# UserComponents.net
KiCad netlist of a schematic drawn in Altium Designer
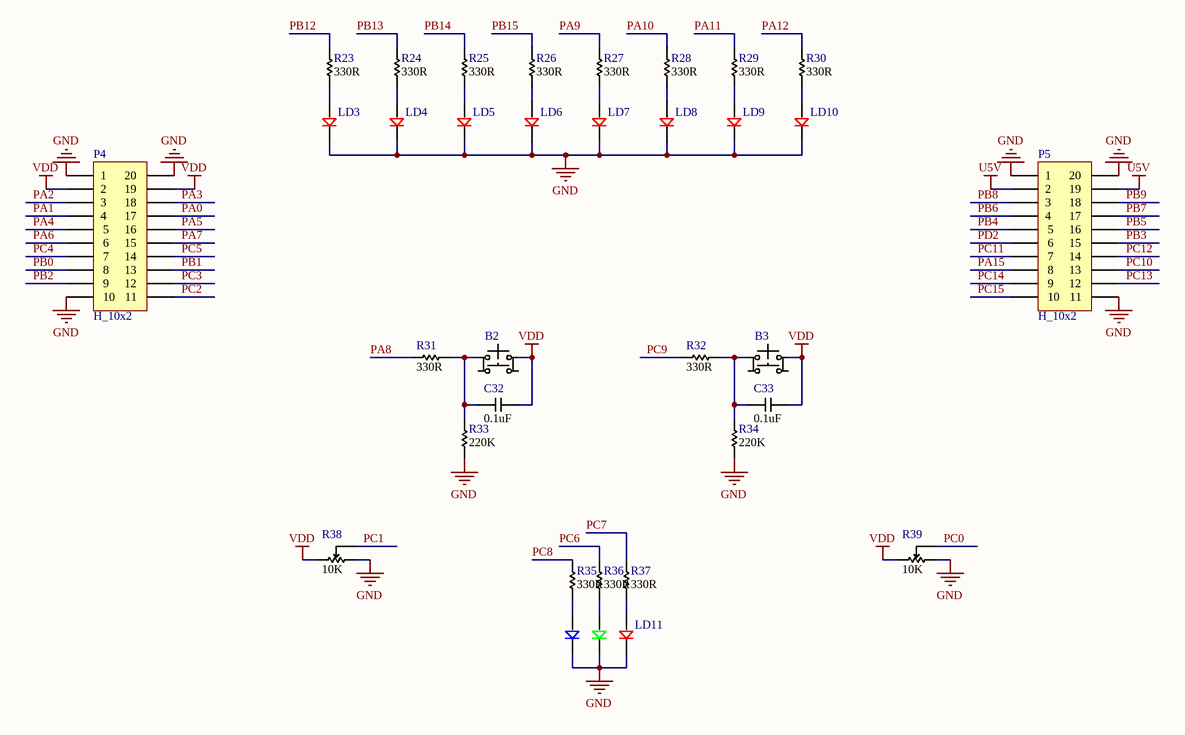
[diagram p0: UserComponents.SchDoc]

(export (version "E")
  (design (tool "Eeschema 10.0.6"))
  (components
    (comp (ref "B2")
      (value "DTSM-65R-V-T/R")
      (footprint "Diptronics_DTSM-65_Red_4")
      (description "Button_SMD_4_6x6x9.5_Diptronics")
      (fields (field (name "MANUFACTURER") "Diptronics"))
      (libsource (lib "Button") (part "DTSM-65R-V-T/R"))
    )
    (comp (ref "B3")
      (value "DTSM-65R-V-T/R")
      (footprint "Diptronics_DTSM-65_Red_4")
      (description "Button_SMD_4_6x6x9.5_Diptronics")
      (fields (field (name "MANUFACTURER") "Diptronics"))
      (libsource (lib "Button") (part "DTSM-65R-V-T/R"))
    )
    (comp (ref "C32")
      (value "0.1uF")
      (footprint "Kemet_0805_X7R")
      (description "Cap_0805_0.1uF_25VDC_Kemet")
      (fields (field (name "MANUFACTURER") "Kemet") (field (name "VOLTAGE") "25VDC"))
      (libsource (lib "Capacitor") (part "C0805C104K3RACTU"))
    )
    (comp (ref "C33")
      (value "0.1uF")
      (footprint "Kemet_0805_X7R")
      (description "Cap_0805_0.1uF_25VDC_Kemet")
      (fields (field (name "MANUFACTURER") "Kemet") (field (name "VOLTAGE") "25VDC"))
      (libsource (lib "Capacitor") (part "C0805C104K3RACTU"))
    )
    (comp (ref "LD3")
      (value "17-21/R6C-AP1Q2L/3T")
      (footprint "Everlight_17-21")
      (description "Led_R_1.7V_25mA_Everlight")
      (fields (field (name "MANUFACTURER") "Everlight"))
      (libsource (lib "LED") (part "17-21/R6C-AP1Q2L/3T"))
    )
    (comp (ref "LD4")
      (value "17-21/R6C-AP1Q2L/3T")
      (footprint "Everlight_17-21")
      (description "Led_R_1.7V_25mA_Everlight")
      (fields (field (name "MANUFACTURER") "Everlight"))
      (libsource (lib "LED") (part "17-21/R6C-AP1Q2L/3T"))
    )
    (comp (ref "LD5")
      (value "17-21/R6C-AP1Q2L/3T")
      (footprint "Everlight_17-21")
      (description "Led_R_1.7V_25mA_Everlight")
      (fields (field (name "MANUFACTURER") "Everlight"))
      (libsource (lib "LED") (part "17-21/R6C-AP1Q2L/3T"))
    )
    (comp (ref "LD6")
      (value "17-21/R6C-AP1Q2L/3T")
      (footprint "Everlight_17-21")
      (description "Led_R_1.7V_25mA_Everlight")
      (fields (field (name "MANUFACTURER") "Everlight"))
      (libsource (lib "LED") (part "17-21/R6C-AP1Q2L/3T"))
    )
    (comp (ref "LD7")
      (value "17-21/R6C-AP1Q2L/3T")
      (footprint "Everlight_17-21")
      (description "Led_R_1.7V_25mA_Everlight")
      (fields (field (name "MANUFACTURER") "Everlight"))
      (libsource (lib "LED") (part "17-21/R6C-AP1Q2L/3T"))
    )
    (comp (ref "LD8")
      (value "17-21/R6C-AP1Q2L/3T")
      (footprint "Everlight_17-21")
      (description "Led_R_1.7V_25mA_Everlight")
      (fields (field (name "MANUFACTURER") "Everlight"))
      (libsource (lib "LED") (part "17-21/R6C-AP1Q2L/3T"))
    )
    (comp (ref "LD9")
      (value "17-21/R6C-AP1Q2L/3T")
      (footprint "Everlight_17-21")
      (description "Led_R_1.7V_25mA_Everlight")
      (fields (field (name "MANUFACTURER") "Everlight"))
      (libsource (lib "LED") (part "17-21/R6C-AP1Q2L/3T"))
    )
    (comp (ref "LD10")
      (value "17-21/R6C-AP1Q2L/3T")
      (footprint "Everlight_17-21")
      (description "Led_R_1.7V_25mA_Everlight")
      (fields (field (name "MANUFACTURER") "Everlight"))
      (libsource (lib "LED") (part "17-21/R6C-AP1Q2L/3T"))
    )
    (comp (ref "LD11")
      (value "HLAF5060H248BS36FU76GCS1")
      (footprint "Honglitronic_5050")
      (description "Led_RGB_1.8-2.8-2.8V_3x90mA_Honglitronic")
      (fields (field (name "MANUFACTURER") "Honglitronic"))
      (libsource (lib "LED") (part "HLAF5060H248BS36FU76GCS1"))
    )
    (comp (ref "P4")
      (value "H_10x2")
      (footprint "HEADER_HDRV20W65P254_10X2_2540X508H945")
      (description "Head_10x2_2.54")
      (libsource (lib "Header") (part "H_10x2"))
    )
    (comp (ref "P5")
      (value "H_10x2")
      (footprint "HEADER_HDRV20W65P254_10X2_2540X508H945")
      (description "Head_10x2_2.54")
      (libsource (lib "Header") (part "H_10x2"))
    )
    (comp (ref "R23")
      (value "330R")
      (footprint "VISHAY_RESC205X125X50L35_30N")
      (description "Res_0805_0R_1/8W_Vishay")
      (fields (field (name "MANUFACTURER") "Vishay") (field (name "POWER") "1/8W"))
      (libsource (lib "Resistor") (part "CRCW08050000Z0EA"))
    )
    (comp (ref "R24")
      (value "330R")
      (footprint "VISHAY_RESC205X125X50L35_30N")
      (description "Res_0805_0R_1/8W_Vishay")
      (fields (field (name "MANUFACTURER") "Vishay") (field (name "POWER") "1/8W"))
      (libsource (lib "Resistor") (part "CRCW08050000Z0EA"))
    )
    (comp (ref "R25")
      (value "330R")
      (footprint "VISHAY_RESC205X125X50L35_30N")
      (description "Res_0805_0R_1/8W_Vishay")
      (fields (field (name "MANUFACTURER") "Vishay") (field (name "POWER") "1/8W"))
      (libsource (lib "Resistor") (part "CRCW08050000Z0EA"))
    )
    (comp (ref "R26")
      (value "330R")
      (footprint "VISHAY_RESC205X125X50L35_30N")
      (description "Res_0805_0R_1/8W_Vishay")
      (fields (field (name "MANUFACTURER") "Vishay") (field (name "POWER") "1/8W"))
      (libsource (lib "Resistor") (part "CRCW08050000Z0EA"))
    )
    (comp (ref "R27")
      (value "330R")
      (footprint "VISHAY_RESC205X125X50L35_30N")
      (description "Res_0805_0R_1/8W_Vishay")
      (fields (field (name "MANUFACTURER") "Vishay") (field (name "POWER") "1/8W"))
      (libsource (lib "Resistor") (part "CRCW08050000Z0EA"))
    )
    (comp (ref "R28")
      (value "330R")
      (footprint "VISHAY_RESC205X125X50L35_30N")
      (description "Res_0805_0R_1/8W_Vishay")
      (fields (field (name "MANUFACTURER") "Vishay") (field (name "POWER") "1/8W"))
      (libsource (lib "Resistor") (part "CRCW08050000Z0EA"))
    )
    (comp (ref "R29")
      (value "330R")
      (footprint "VISHAY_RESC205X125X50L35_30N")
      (description "Res_0805_0R_1/8W_Vishay")
      (fields (field (name "MANUFACTURER") "Vishay") (field (name "POWER") "1/8W"))
      (libsource (lib "Resistor") (part "CRCW08050000Z0EA"))
    )
    (comp (ref "R30")
      (value "330R")
      (footprint "VISHAY_RESC205X125X50L35_30N")
      (description "Res_0805_0R_1/8W_Vishay")
      (fields (field (name "MANUFACTURER") "Vishay") (field (name "POWER") "1/8W"))
      (libsource (lib "Resistor") (part "CRCW08050000Z0EA"))
    )
    (comp (ref "R31")
      (value "330R")
      (footprint "VISHAY_RESC205X125X50L35_30N")
      (description "Res_0805_0R_1/8W_Vishay")
      (fields (field (name "MANUFACTURER") "Vishay") (field (name "POWER") "1/8W"))
      (libsource (lib "Resistor") (part "CRCW08050000Z0EA"))
    )
    (comp (ref "R32")
      (value "330R")
      (footprint "VISHAY_RESC205X125X50L35_30N")
      (description "Res_0805_0R_1/8W_Vishay")
      (fields (field (name "MANUFACTURER") "Vishay") (field (name "POWER") "1/8W"))
      (libsource (lib "Resistor") (part "CRCW08050000Z0EA"))
    )
    (comp (ref "R33")
      (value "220K")
      (footprint "VISHAY_RESC205X125X50L35_30N")
      (description "Res_0805_0R_1/8W_Vishay")
      (fields (field (name "MANUFACTURER") "Vishay") (field (name "POWER") "1/8W"))
      (libsource (lib "Resistor") (part "CRCW08050000Z0EA"))
    )
    (comp (ref "R34")
      (value "220K")
      (footprint "VISHAY_RESC205X125X50L35_30N")
      (description "Res_0805_0R_1/8W_Vishay")
      (fields (field (name "MANUFACTURER") "Vishay") (field (name "POWER") "1/8W"))
      (libsource (lib "Resistor") (part "CRCW08050000Z0EA"))
    )
    (comp (ref "R35")
      (value "330R")
      (footprint "VISHAY_RESC205X125X50L35_30N")
      (description "Res_0805_0R_1/8W_Vishay")
      (fields (field (name "MANUFACTURER") "Vishay") (field (name "POWER") "1/8W"))
      (libsource (lib "Resistor") (part "CRCW08050000Z0EA"))
    )
    (comp (ref "R36")
      (value "330R")
      (footprint "VISHAY_RESC205X125X50L35_30N")
      (description "Res_0805_0R_1/8W_Vishay")
      (fields (field (name "MANUFACTURER") "Vishay") (field (name "POWER") "1/8W"))
      (libsource (lib "Resistor") (part "CRCW08050000Z0EA"))
    )
    (comp (ref "R37")
      (value "330R")
      (footprint "VISHAY_RESC205X125X50L35_30N")
      (description "Res_0805_0R_1/8W_Vishay")
      (fields (field (name "MANUFACTURER") "Vishay") (field (name "POWER") "1/8W"))
      (libsource (lib "Resistor") (part "CRCW08050000Z0EA"))
    )
    (comp (ref "R38")
      (value "10K")
      (footprint "Bonens_3386F")
      (description "Trimpot_10K_Bonens")
      (fields (field (name "MANUFACTURER") "Bonens") (field (name "Comment") "3386F-1-103LF-BN"))
      (libsource (lib "Resistor") (part "3386F-1-103LF-BN"))
    )
    (comp (ref "R39")
      (value "10K")
      (footprint "Bonens_3386F")
      (description "Trimpot_10K_Bonens")
      (fields (field (name "MANUFACTURER") "Bonens") (field (name "Comment") "3386F-1-103LF-BN"))
      (libsource (lib "Resistor") (part "3386F-1-103LF-BN"))
    )
  )
  (nets
    (net (code "1") (name "/PA0") (class "Default")
      (node (ref "P4") (pin "17") (pinfunction "17_17") (pintype "passive"))
    )
    (net (code "2") (name "/PA1") (class "Default")
      (node (ref "P4") (pin "4") (pinfunction "4_4") (pintype "passive"))
    )
    (net (code "3") (name "/PA2") (class "Default")
      (node (ref "P4") (pin "3") (pinfunction "3_3") (pintype "passive"))
    )
    (net (code "4") (name "/PA3") (class "Default")
      (node (ref "P4") (pin "18") (pinfunction "18_18") (pintype "passive"))
    )
    (net (code "5") (name "/PA4") (class "Default")
      (node (ref "P4") (pin "5") (pinfunction "5_5") (pintype "passive"))
    )
    (net (code "6") (name "/PA5") (class "Default")
      (node (ref "P4") (pin "16") (pinfunction "16_16") (pintype "passive"))
    )
    (net (code "7") (name "/PA6") (class "Default")
      (node (ref "P4") (pin "6") (pinfunction "6_6") (pintype "passive"))
    )
    (net (code "8") (name "/PA7") (class "Default")
      (node (ref "P4") (pin "15") (pinfunction "15_15") (pintype "passive"))
    )
    (net (code "9") (name "/PA8") (class "Default")
      (node (ref "R31") (pin "1") (pinfunction "1_1") (pintype "passive"))
    )
    (net (code "10") (name "/PA9") (class "Default")
      (node (ref "R27") (pin "2") (pinfunction "2_2") (pintype "passive"))
    )
    (net (code "11") (name "/PA10") (class "Default")
      (node (ref "R28") (pin "2") (pinfunction "2_2") (pintype "passive"))
    )
    (net (code "12") (name "/PA11") (class "Default")
      (node (ref "R29") (pin "2") (pinfunction "2_2") (pintype "passive"))
    )
    (net (code "13") (name "/PA12") (class "Default")
      (node (ref "R30") (pin "2") (pinfunction "2_2") (pintype "passive"))
    )
    (net (code "14") (name "/PA15") (class "Default")
      (node (ref "P5") (pin "8") (pinfunction "8_8") (pintype "passive"))
    )
    (net (code "15") (name "/PB0") (class "Default")
      (node (ref "P4") (pin "8") (pinfunction "8_8") (pintype "passive"))
    )
    (net (code "16") (name "/PB1") (class "Default")
      (node (ref "P4") (pin "13") (pinfunction "13_13") (pintype "passive"))
    )
    (net (code "17") (name "/PB2") (class "Default")
      (node (ref "P4") (pin "9") (pinfunction "9_9") (pintype "passive"))
    )
    (net (code "18") (name "/PB3") (class "Default")
      (node (ref "P5") (pin "15") (pinfunction "15_15") (pintype "passive"))
    )
    (net (code "19") (name "/PB4") (class "Default")
      (node (ref "P5") (pin "5") (pinfunction "5_5") (pintype "passive"))
    )
    (net (code "20") (name "/PB5") (class "Default")
      (node (ref "P5") (pin "16") (pinfunction "16_16") (pintype "passive"))
    )
    (net (code "21") (name "/PB6") (class "Default")
      (node (ref "P5") (pin "4") (pinfunction "4_4") (pintype "passive"))
    )
    (net (code "22") (name "/PB7") (class "Default")
      (node (ref "P5") (pin "17") (pinfunction "17_17") (pintype "passive"))
    )
    (net (code "23") (name "/PB8") (class "Default")
      (node (ref "P5") (pin "3") (pinfunction "3_3") (pintype "passive"))
    )
    (net (code "24") (name "/PB9") (class "Default")
      (node (ref "P5") (pin "18") (pinfunction "18_18") (pintype "passive"))
    )
    (net (code "25") (name "/PB12") (class "Default")
      (node (ref "R23") (pin "2") (pinfunction "2_2") (pintype "passive"))
    )
    (net (code "26") (name "/PB13") (class "Default")
      (node (ref "R24") (pin "2") (pinfunction "2_2") (pintype "passive"))
    )
    (net (code "27") (name "/PB14") (class "Default")
      (node (ref "R25") (pin "2") (pinfunction "2_2") (pintype "passive"))
    )
    (net (code "28") (name "/PB15") (class "Default")
      (node (ref "R26") (pin "2") (pinfunction "2_2") (pintype "passive"))
    )
    (net (code "29") (name "/PC0") (class "Default")
      (node (ref "R39") (pin "2") (pinfunction "2_2") (pintype "passive"))
    )
    (net (code "30") (name "/PC1") (class "Default")
      (node (ref "R38") (pin "2") (pinfunction "2_2") (pintype "passive"))
    )
    (net (code "31") (name "/PC2") (class "Default")
      (node (ref "P4") (pin "11") (pinfunction "11_11") (pintype "passive"))
    )
    (net (code "32") (name "/PC3") (class "Default")
      (node (ref "P4") (pin "12") (pinfunction "12_12") (pintype "passive"))
    )
    (net (code "33") (name "/PC4") (class "Default")
      (node (ref "P4") (pin "7") (pinfunction "7_7") (pintype "passive"))
    )
    (net (code "34") (name "/PC5") (class "Default")
      (node (ref "P4") (pin "14") (pinfunction "14_14") (pintype "passive"))
    )
    (net (code "35") (name "/PC6") (class "Default")
      (node (ref "R36") (pin "2") (pinfunction "2_2") (pintype "passive"))
    )
    (net (code "36") (name "/PC7") (class "Default")
      (node (ref "R37") (pin "2") (pinfunction "2_2") (pintype "passive"))
    )
    (net (code "37") (name "/PC8") (class "Default")
      (node (ref "R35") (pin "2") (pinfunction "2_2") (pintype "passive"))
    )
    (net (code "38") (name "/PC9") (class "Default")
      (node (ref "R32") (pin "1") (pinfunction "1_1") (pintype "passive"))
    )
    (net (code "39") (name "/PC10") (class "Default")
      (node (ref "P5") (pin "13") (pinfunction "13_13") (pintype "passive"))
    )
    (net (code "40") (name "/PC11") (class "Default")
      (node (ref "P5") (pin "7") (pinfunction "7_7") (pintype "passive"))
    )
    (net (code "41") (name "/PC12") (class "Default")
      (node (ref "P5") (pin "14") (pinfunction "14_14") (pintype "passive"))
    )
    (net (code "42") (name "/PC13") (class "Default")
      (node (ref "P5") (pin "12") (pinfunction "12_12") (pintype "passive"))
    )
    (net (code "43") (name "/PC14") (class "Default")
      (node (ref "P5") (pin "9") (pinfunction "9_9") (pintype "passive"))
    )
    (net (code "44") (name "/PC15") (class "Default")
      (node (ref "P5") (pin "10") (pinfunction "10_10") (pintype "passive"))
    )
    (net (code "45") (name "/PD2") (class "Default")
      (node (ref "P5") (pin "6") (pinfunction "6_6") (pintype "passive"))
    )
    (net (code "46") (name "GND") (class "Default")
      (node (ref "LD10") (pin "2") (pinfunction "R-_2") (pintype "passive"))
      (node (ref "LD11") (pin "4") (pinfunction "B-_4") (pintype "passive"))
      (node (ref "LD11") (pin "5") (pinfunction "R-_5") (pintype "passive"))
      (node (ref "LD11") (pin "6") (pinfunction "G-_6") (pintype "passive"))
      (node (ref "LD3") (pin "2") (pinfunction "R-_2") (pintype "passive"))
      (node (ref "LD4") (pin "2") (pinfunction "R-_2") (pintype "passive"))
      (node (ref "LD5") (pin "2") (pinfunction "R-_2") (pintype "passive"))
      (node (ref "LD6") (pin "2") (pinfunction "R-_2") (pintype "passive"))
      (node (ref "LD7") (pin "2") (pinfunction "R-_2") (pintype "passive"))
      (node (ref "LD8") (pin "2") (pinfunction "R-_2") (pintype "passive"))
      (node (ref "LD9") (pin "2") (pinfunction "R-_2") (pintype "passive"))
      (node (ref "P4") (pin "1") (pinfunction "1_1") (pintype "passive"))
      (node (ref "P4") (pin "10") (pinfunction "10_10") (pintype "passive"))
      (node (ref "P4") (pin "20") (pinfunction "20_20") (pintype "passive"))
      (node (ref "P5") (pin "1") (pinfunction "1_1") (pintype "passive"))
      (node (ref "P5") (pin "11") (pinfunction "11_11") (pintype "passive"))
      (node (ref "P5") (pin "20") (pinfunction "20_20") (pintype "passive"))
      (node (ref "R33") (pin "2") (pinfunction "2_2") (pintype "passive"))
      (node (ref "R34") (pin "2") (pinfunction "2_2") (pintype "passive"))
      (node (ref "R38") (pin "3") (pinfunction "3_3") (pintype "passive"))
      (node (ref "R39") (pin "3") (pinfunction "3_3") (pintype "passive"))
    )
    (net (code "47") (name "Net-(B2-Pad1)") (class "Default")
      (node (ref "B2") (pin "1") (pinfunction "1_1") (pintype "passive"))
      (node (ref "C32") (pin "1") (pinfunction "1_1") (pintype "passive"))
      (node (ref "R31") (pin "2") (pinfunction "2_2") (pintype "passive"))
      (node (ref "R33") (pin "1") (pinfunction "1_1") (pintype "passive"))
    )
    (net (code "48") (name "Net-(B3-Pad1)") (class "Default")
      (node (ref "B3") (pin "1") (pinfunction "1_1") (pintype "passive"))
      (node (ref "C33") (pin "1") (pinfunction "1_1") (pintype "passive"))
      (node (ref "R32") (pin "2") (pinfunction "2_2") (pintype "passive"))
      (node (ref "R34") (pin "1") (pinfunction "1_1") (pintype "passive"))
    )
    (net (code "49") (name "Net-(LD3-R+)") (class "Default")
      (node (ref "LD3") (pin "1") (pinfunction "R+_1") (pintype "passive"))
      (node (ref "R23") (pin "1") (pinfunction "1_1") (pintype "passive"))
    )
    (net (code "50") (name "Net-(LD4-R+)") (class "Default")
      (node (ref "LD4") (pin "1") (pinfunction "R+_1") (pintype "passive"))
      (node (ref "R24") (pin "1") (pinfunction "1_1") (pintype "passive"))
    )
    (net (code "51") (name "Net-(LD5-R+)") (class "Default")
      (node (ref "LD5") (pin "1") (pinfunction "R+_1") (pintype "passive"))
      (node (ref "R25") (pin "1") (pinfunction "1_1") (pintype "passive"))
    )
    (net (code "52") (name "Net-(LD6-R+)") (class "Default")
      (node (ref "LD6") (pin "1") (pinfunction "R+_1") (pintype "passive"))
      (node (ref "R26") (pin "1") (pinfunction "1_1") (pintype "passive"))
    )
    (net (code "53") (name "Net-(LD7-R+)") (class "Default")
      (node (ref "LD7") (pin "1") (pinfunction "R+_1") (pintype "passive"))
      (node (ref "R27") (pin "1") (pinfunction "1_1") (pintype "passive"))
    )
    (net (code "54") (name "Net-(LD8-R+)") (class "Default")
      (node (ref "LD8") (pin "1") (pinfunction "R+_1") (pintype "passive"))
      (node (ref "R28") (pin "1") (pinfunction "1_1") (pintype "passive"))
    )
    (net (code "55") (name "Net-(LD9-R+)") (class "Default")
      (node (ref "LD9") (pin "1") (pinfunction "R+_1") (pintype "passive"))
      (node (ref "R29") (pin "1") (pinfunction "1_1") (pintype "passive"))
    )
    (net (code "56") (name "Net-(LD10-R+)") (class "Default")
      (node (ref "LD10") (pin "1") (pinfunction "R+_1") (pintype "passive"))
      (node (ref "R30") (pin "1") (pinfunction "1_1") (pintype "passive"))
    )
    (net (code "57") (name "Net-(LD11-B+)") (class "Default")
      (node (ref "LD11") (pin "3") (pinfunction "B+_3") (pintype "passive"))
      (node (ref "R35") (pin "1") (pinfunction "1_1") (pintype "passive"))
    )
    (net (code "58") (name "Net-(LD11-G+)") (class "Default")
      (node (ref "LD11") (pin "1") (pinfunction "G+_1") (pintype "passive"))
      (node (ref "R36") (pin "1") (pinfunction "1_1") (pintype "passive"))
    )
    (net (code "59") (name "Net-(LD11-R+)") (class "Default")
      (node (ref "LD11") (pin "2") (pinfunction "R+_2") (pintype "passive"))
      (node (ref "R37") (pin "1") (pinfunction "1_1") (pintype "passive"))
    )
    (net (code "60") (name "U5V") (class "Default")
      (node (ref "P5") (pin "19") (pinfunction "19_19") (pintype "passive"))
      (node (ref "P5") (pin "2") (pinfunction "2_2") (pintype "passive"))
    )
    (net (code "61") (name "VDD") (class "Default")
      (node (ref "B2") (pin "3") (pinfunction "3_3") (pintype "passive"))
      (node (ref "B3") (pin "3") (pinfunction "3_3") (pintype "passive"))
      (node (ref "C32") (pin "2") (pinfunction "2_2") (pintype "passive"))
      (node (ref "C33") (pin "2") (pinfunction "2_2") (pintype "passive"))
      (node (ref "P4") (pin "19") (pinfunction "19_19") (pintype "passive"))
      (node (ref "P4") (pin "2") (pinfunction "2_2") (pintype "passive"))
      (node (ref "R38") (pin "1") (pinfunction "1_1") (pintype "passive"))
      (node (ref "R39") (pin "1") (pinfunction "1_1") (pintype "passive"))
    )
    (net (code "62") (name "unconnected-(B2-Pad2)") (class "Default")
      (node (ref "B2") (pin "2") (pinfunction "2_2") (pintype "passive"))
    )
    (net (code "63") (name "unconnected-(B2-Pad4)") (class "Default")
      (node (ref "B2") (pin "4") (pinfunction "4_4") (pintype "passive"))
    )
    (net (code "64") (name "unconnected-(B3-Pad2)") (class "Default")
      (node (ref "B3") (pin "2") (pinfunction "2_2") (pintype "passive"))
    )
    (net (code "65") (name "unconnected-(B3-Pad4)") (class "Default")
      (node (ref "B3") (pin "4") (pinfunction "4_4") (pintype "passive"))
    )
  )
)
